# Half_Bridge.net
KiCad netlist of a schematic drawn in Altium Designer
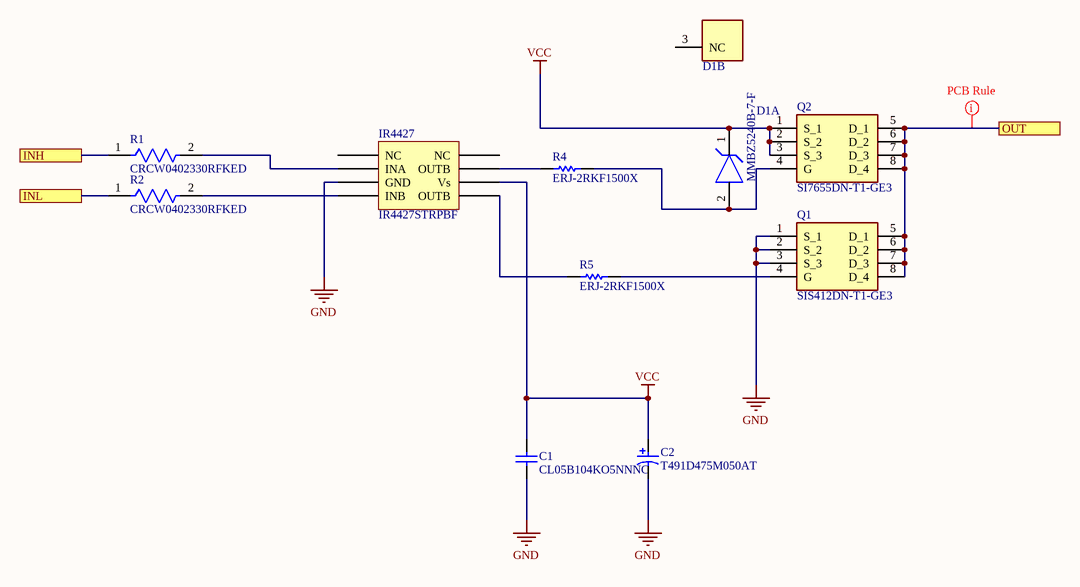
[diagram p0: Half_Bridge.SchDoc]

(export (version "E")
  (design (tool "Eeschema 10.0.6"))
  (components
    (comp (ref "C1")
      (value "CL05B104KO5NNNC")
      (footprint "CAPC1050X55X23ML05T13")
      (description "Chip Capacitor, 100 nF, +/- 10%, 16 V, -55 to 125 degC, 0402 (1005 Metric), RoHS, Tape and Reel")
      (fields (field (name "MANUFACTURER") "Samsung Electro-Mechanics"))
      (libsource (lib "Altium Content Vault") (part "CAP-NP-2"))
    )
    (comp (ref "C2")
      (value "T491D475M050AT")
      (footprint "KEMT-T491-D_L")
      (fields (field (name "VOLTAGE") "50VDC") (field (name "MANUFACTURER") "Kemet"))
      (libsource (lib "Altium Content Vault") (part "CAP-P-2"))
    )
    (comp (ref "D1")
      (value "MMBZ5240B-7-F")
      (footprint "Diodes_SOT23_0")
      (libsource (lib "Diode_Diodes_MMBZ5240B-7-F_eec") (part "MMBZ5240B-7-F"))
    )
    (comp (ref "IR4427")
      (value "IR4427STRPBF")
      (footprint "IR4427-PCB")
      (description "IC DRIVER DUAL LOW SIDE 8-DIP")
      (libsource (lib "Schlib1") (part "IR4427"))
    )
    (comp (ref "Q1")
      (value "SIS412DN-T1-GE3")
      (footprint "POWERPAK-1212-8")
      (description "MOSFET (N-Channel)")
      (fields (field (name "MOUSER2 PART NUMBER") "781-SIS412DN-T1-GE3"))
      (libsource (lib "SamacSys") (part "SIS412DN-T1-GE3"))
    )
    (comp (ref "Q2")
      (value "SI7655DN-T1-GE3")
      (footprint "PcbLib1:POWERPAK-1212-8")
      (description "MOSFET (P-Channel)")
      (fields (field (name "MOUSER PART NUMBER") "78-SI7655DN-T1-GE3"))
      (libsource (lib "Schlib1") (part "SI7655DN-T1-GE3"))
    )
    (comp (ref "R1")
      (value "CRCW0402330RFKED")
      (footprint "FP-CRCW0402-e3-MFG")
      (description "RES Thick Film, 330Ω, 1%, 0.063W, 100ppm/°C, 0402")
      (fields (field (name "TOLERANCE") "1%"))
      (libsource (lib "Altium Content Vault") (part "1029c3af85768c4190bb7ad29bc67b5"))
    )
    (comp (ref "R2")
      (value "CRCW0402330RFKED")
      (footprint "FP-CRCW0402-e3-MFG")
      (description "RES Thick Film, 330Ω, 1%, 0.063W, 100ppm/°C, 0402")
      (fields (field (name "TOLERANCE") "1%"))
      (libsource (lib "Altium Content Vault") (part "1029c3af85768c4190bb7ad29bc67b5"))
    )
    (comp (ref "R4")
      (value "ERJ-2RKF1500X")
      (footprint "RESC1005X40X25NL05T05")
      (fields (field (name "MANUFACTURER") "Panasonic"))
      (libsource (lib "Altium Content Vault") (part "RES"))
    )
    (comp (ref "R5")
      (value "ERJ-2RKF1500X")
      (footprint "RESC1005X40X25NL05T05")
      (fields (field (name "MANUFACTURER") "Panasonic"))
      (libsource (lib "Altium Content Vault") (part "RES"))
    )
  )
  (nets
    (net (code "1") (name "/INH") (class "Default")
      (node (ref "R1") (pin "1") (pinfunction "1_1") (pintype "passive"))
    )
    (net (code "2") (name "/INL") (class "Default")
      (node (ref "R2") (pin "1") (pinfunction "1_1") (pintype "passive"))
    )
    (net (code "3") (name "/OUT") (class "Default")
      (node (ref "Q1") (pin "5") (pinfunction "D_1_5") (pintype "passive"))
      (node (ref "Q1") (pin "6") (pinfunction "D_2_6") (pintype "passive"))
      (node (ref "Q1") (pin "7") (pinfunction "D_3_7") (pintype "passive"))
      (node (ref "Q1") (pin "8") (pinfunction "D_4_8") (pintype "passive"))
      (node (ref "Q2") (pin "5") (pinfunction "D_1_5") (pintype "passive"))
      (node (ref "Q2") (pin "6") (pinfunction "D_2_6") (pintype "passive"))
      (node (ref "Q2") (pin "7") (pinfunction "D_3_7") (pintype "passive"))
      (node (ref "Q2") (pin "8") (pinfunction "D_4_8") (pintype "passive"))
    )
    (net (code "4") (name "GND") (class "Default")
      (node (ref "C1") (pin "1") (pinfunction "1_1") (pintype "passive"))
      (node (ref "C2") (pin "2") (pinfunction "2_2") (pintype "passive"))
      (node (ref "IR4427") (pin "3") (pinfunction "GND_3") (pintype "passive"))
      (node (ref "Q1") (pin "1") (pinfunction "S_1_1") (pintype "passive"))
      (node (ref "Q1") (pin "2") (pinfunction "S_2_2") (pintype "passive"))
      (node (ref "Q1") (pin "3") (pinfunction "S_3_3") (pintype "passive"))
    )
    (net (code "5") (name "Net-(D1A-A)") (class "Default")
      (node (ref "D1") (pin "2") (pinfunction "A_2") (pintype "passive"))
      (node (ref "Q2") (pin "4") (pinfunction "G_4") (pintype "passive"))
      (node (ref "R4") (pin "2") (pinfunction "2_2") (pintype "passive"))
    )
    (net (code "6") (name "Net-(IR4427-INA)") (class "Default")
      (node (ref "IR4427") (pin "2") (pinfunction "INA_2") (pintype "passive"))
      (node (ref "R1") (pin "2") (pinfunction "2_2") (pintype "passive"))
    )
    (net (code "7") (name "Net-(IR4427-INB)") (class "Default")
      (node (ref "IR4427") (pin "4") (pinfunction "INB_4") (pintype "passive"))
      (node (ref "R2") (pin "2") (pinfunction "2_2") (pintype "passive"))
    )
    (net (code "8") (name "Net-(IR4427-OUTB-Pad5)") (class "Default")
      (node (ref "IR4427") (pin "5") (pinfunction "OUTB_5") (pintype "passive"))
      (node (ref "R5") (pin "1") (pinfunction "1_1") (pintype "passive"))
    )
    (net (code "9") (name "Net-(IR4427-OUTB-Pad7)") (class "Default")
      (node (ref "IR4427") (pin "7") (pinfunction "OUTB_7") (pintype "passive"))
      (node (ref "R4") (pin "1") (pinfunction "1_1") (pintype "passive"))
    )
    (net (code "10") (name "Net-(Q1-G)") (class "Default")
      (node (ref "Q1") (pin "4") (pinfunction "G_4") (pintype "passive"))
      (node (ref "R5") (pin "2") (pinfunction "2_2") (pintype "passive"))
    )
    (net (code "11") (name "VCC") (class "Default")
      (node (ref "C1") (pin "2") (pinfunction "2_2") (pintype "passive"))
      (node (ref "C2") (pin "1") (pinfunction "1_1") (pintype "passive"))
      (node (ref "D1") (pin "1") (pinfunction "C_1") (pintype "passive"))
      (node (ref "IR4427") (pin "6") (pinfunction "Vs_6") (pintype "passive"))
      (node (ref "Q2") (pin "1") (pinfunction "S_1_1") (pintype "passive"))
      (node (ref "Q2") (pin "2") (pinfunction "S_2_2") (pintype "passive"))
      (node (ref "Q2") (pin "3") (pinfunction "S_3_3") (pintype "passive"))
    )
    (net (code "12") (name "unconnected-(D1B-NC-Pad3)") (class "Default")
      (node (ref "D1") (pin "3") (pinfunction "NC_3") (pintype "passive"))
    )
    (net (code "13") (name "unconnected-(IR4427-NC-Pad1)") (class "Default")
      (node (ref "IR4427") (pin "1") (pinfunction "NC_1") (pintype "passive"))
    )
    (net (code "14") (name "unconnected-(IR4427-NC-Pad8)") (class "Default")
      (node (ref "IR4427") (pin "8") (pinfunction "NC_8") (pintype "passive"))
    )
  )
)
